# v1.net
KiCad netlist of a schematic drawn in EAGLE
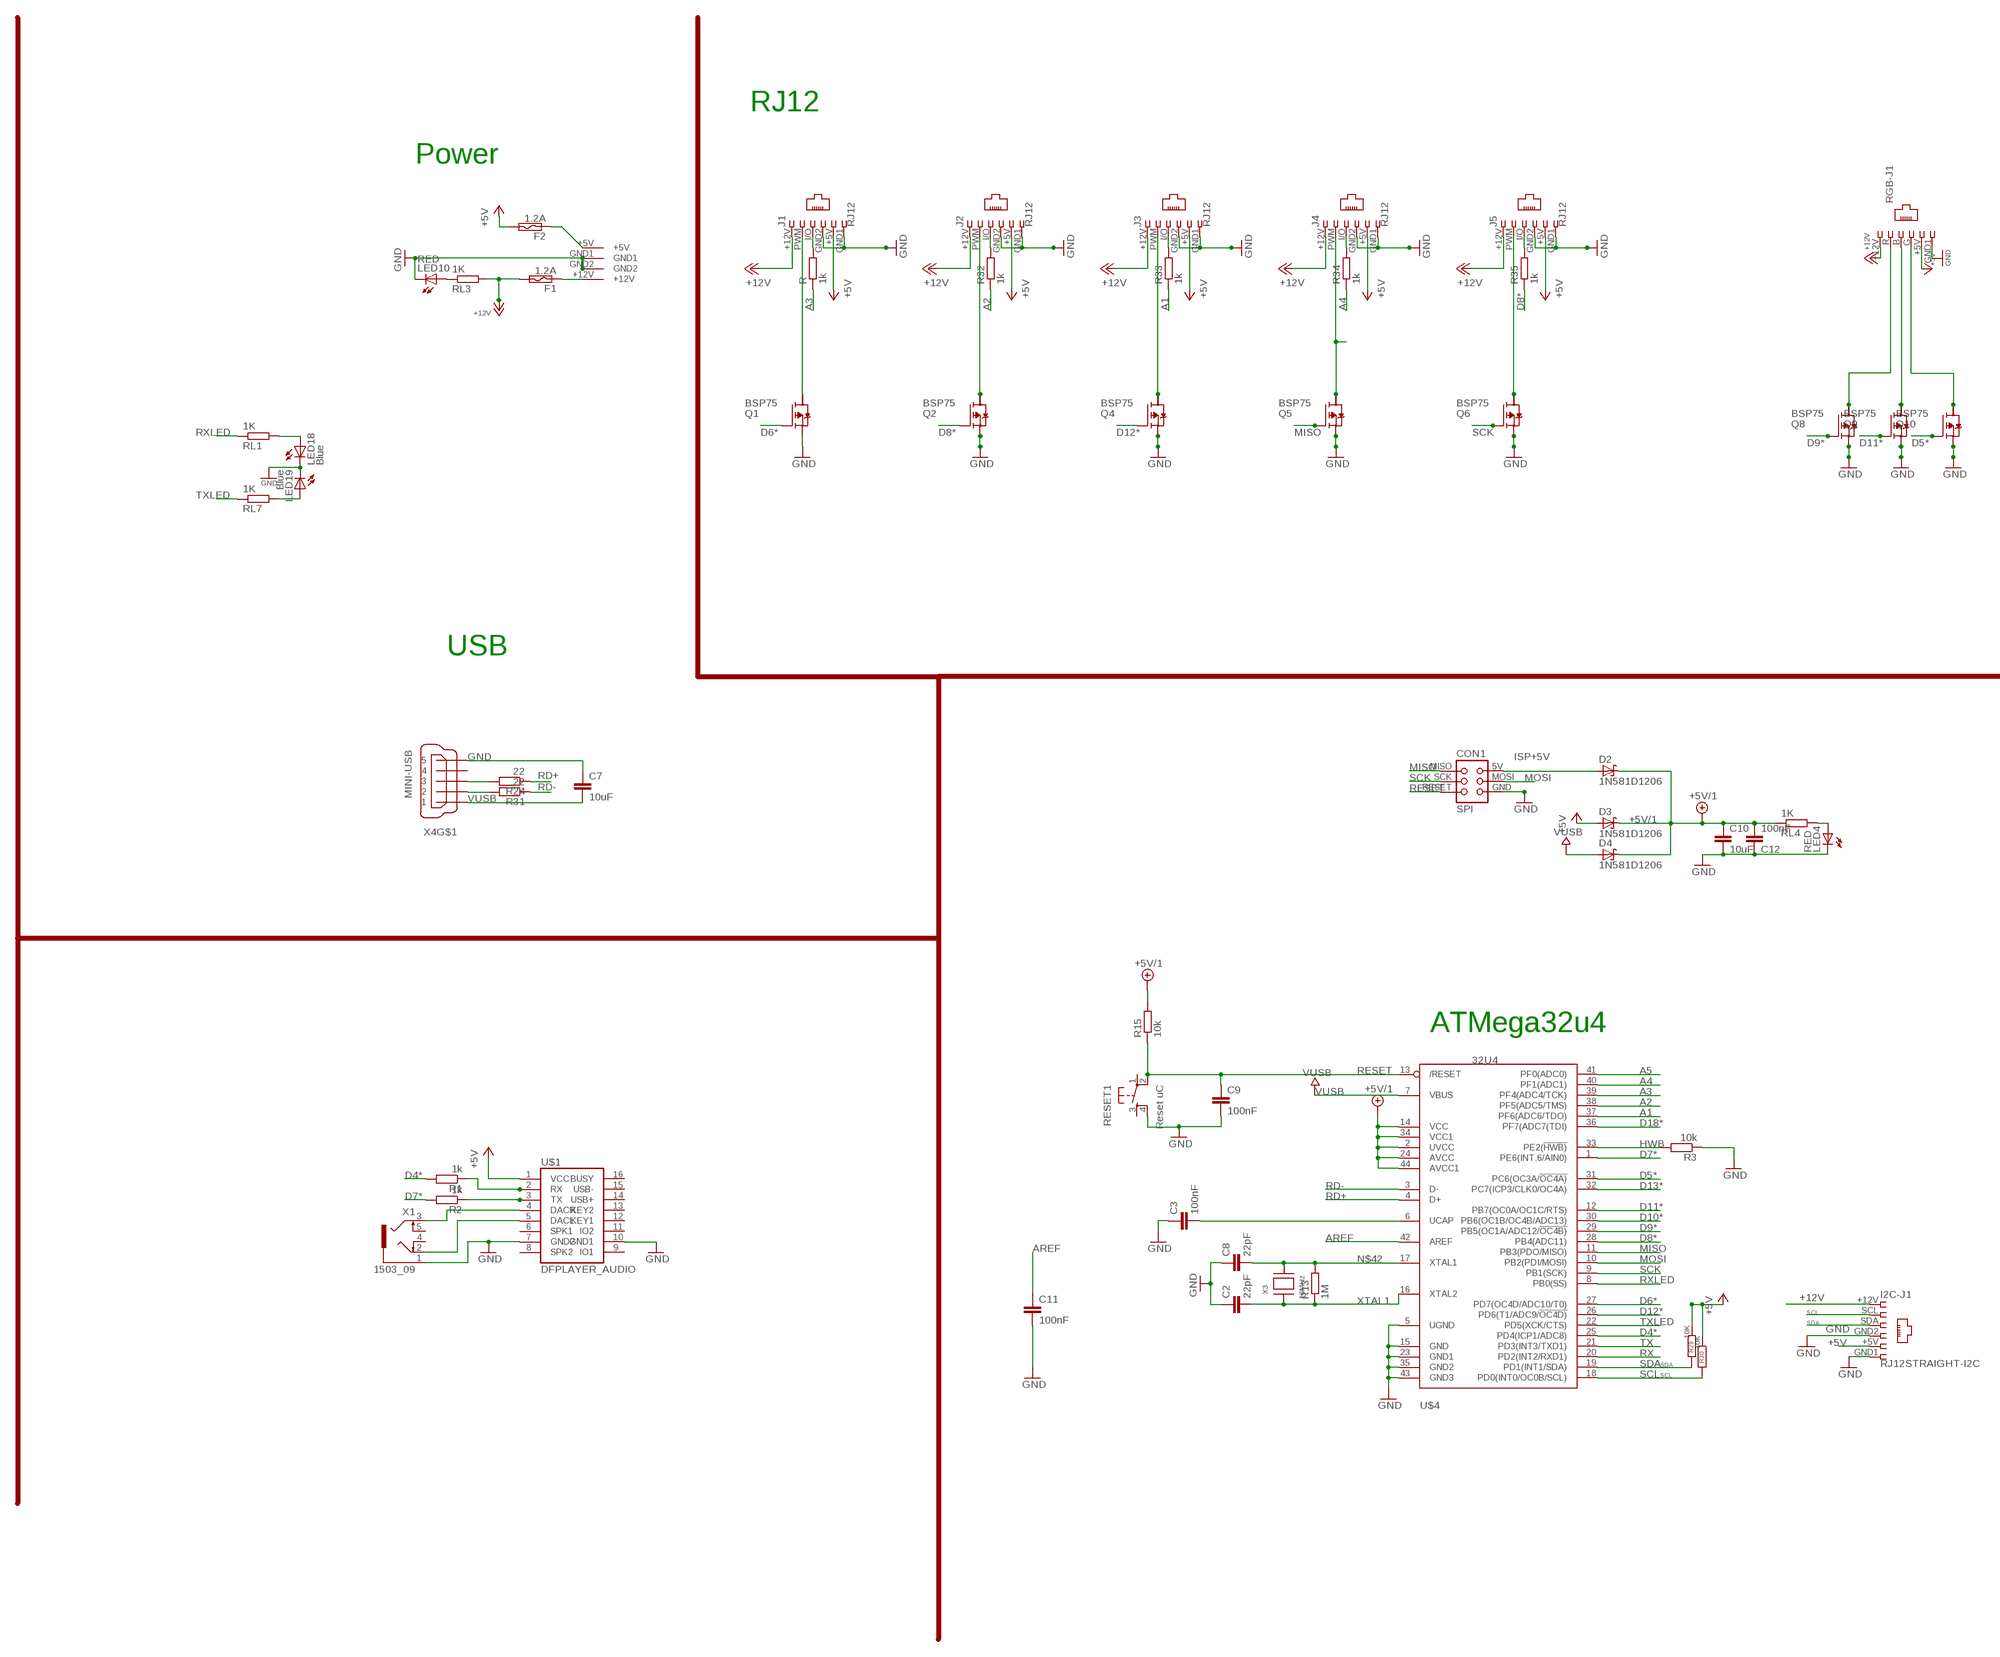
[diagram p0: schematic, sheet 1, part 1 of 2]
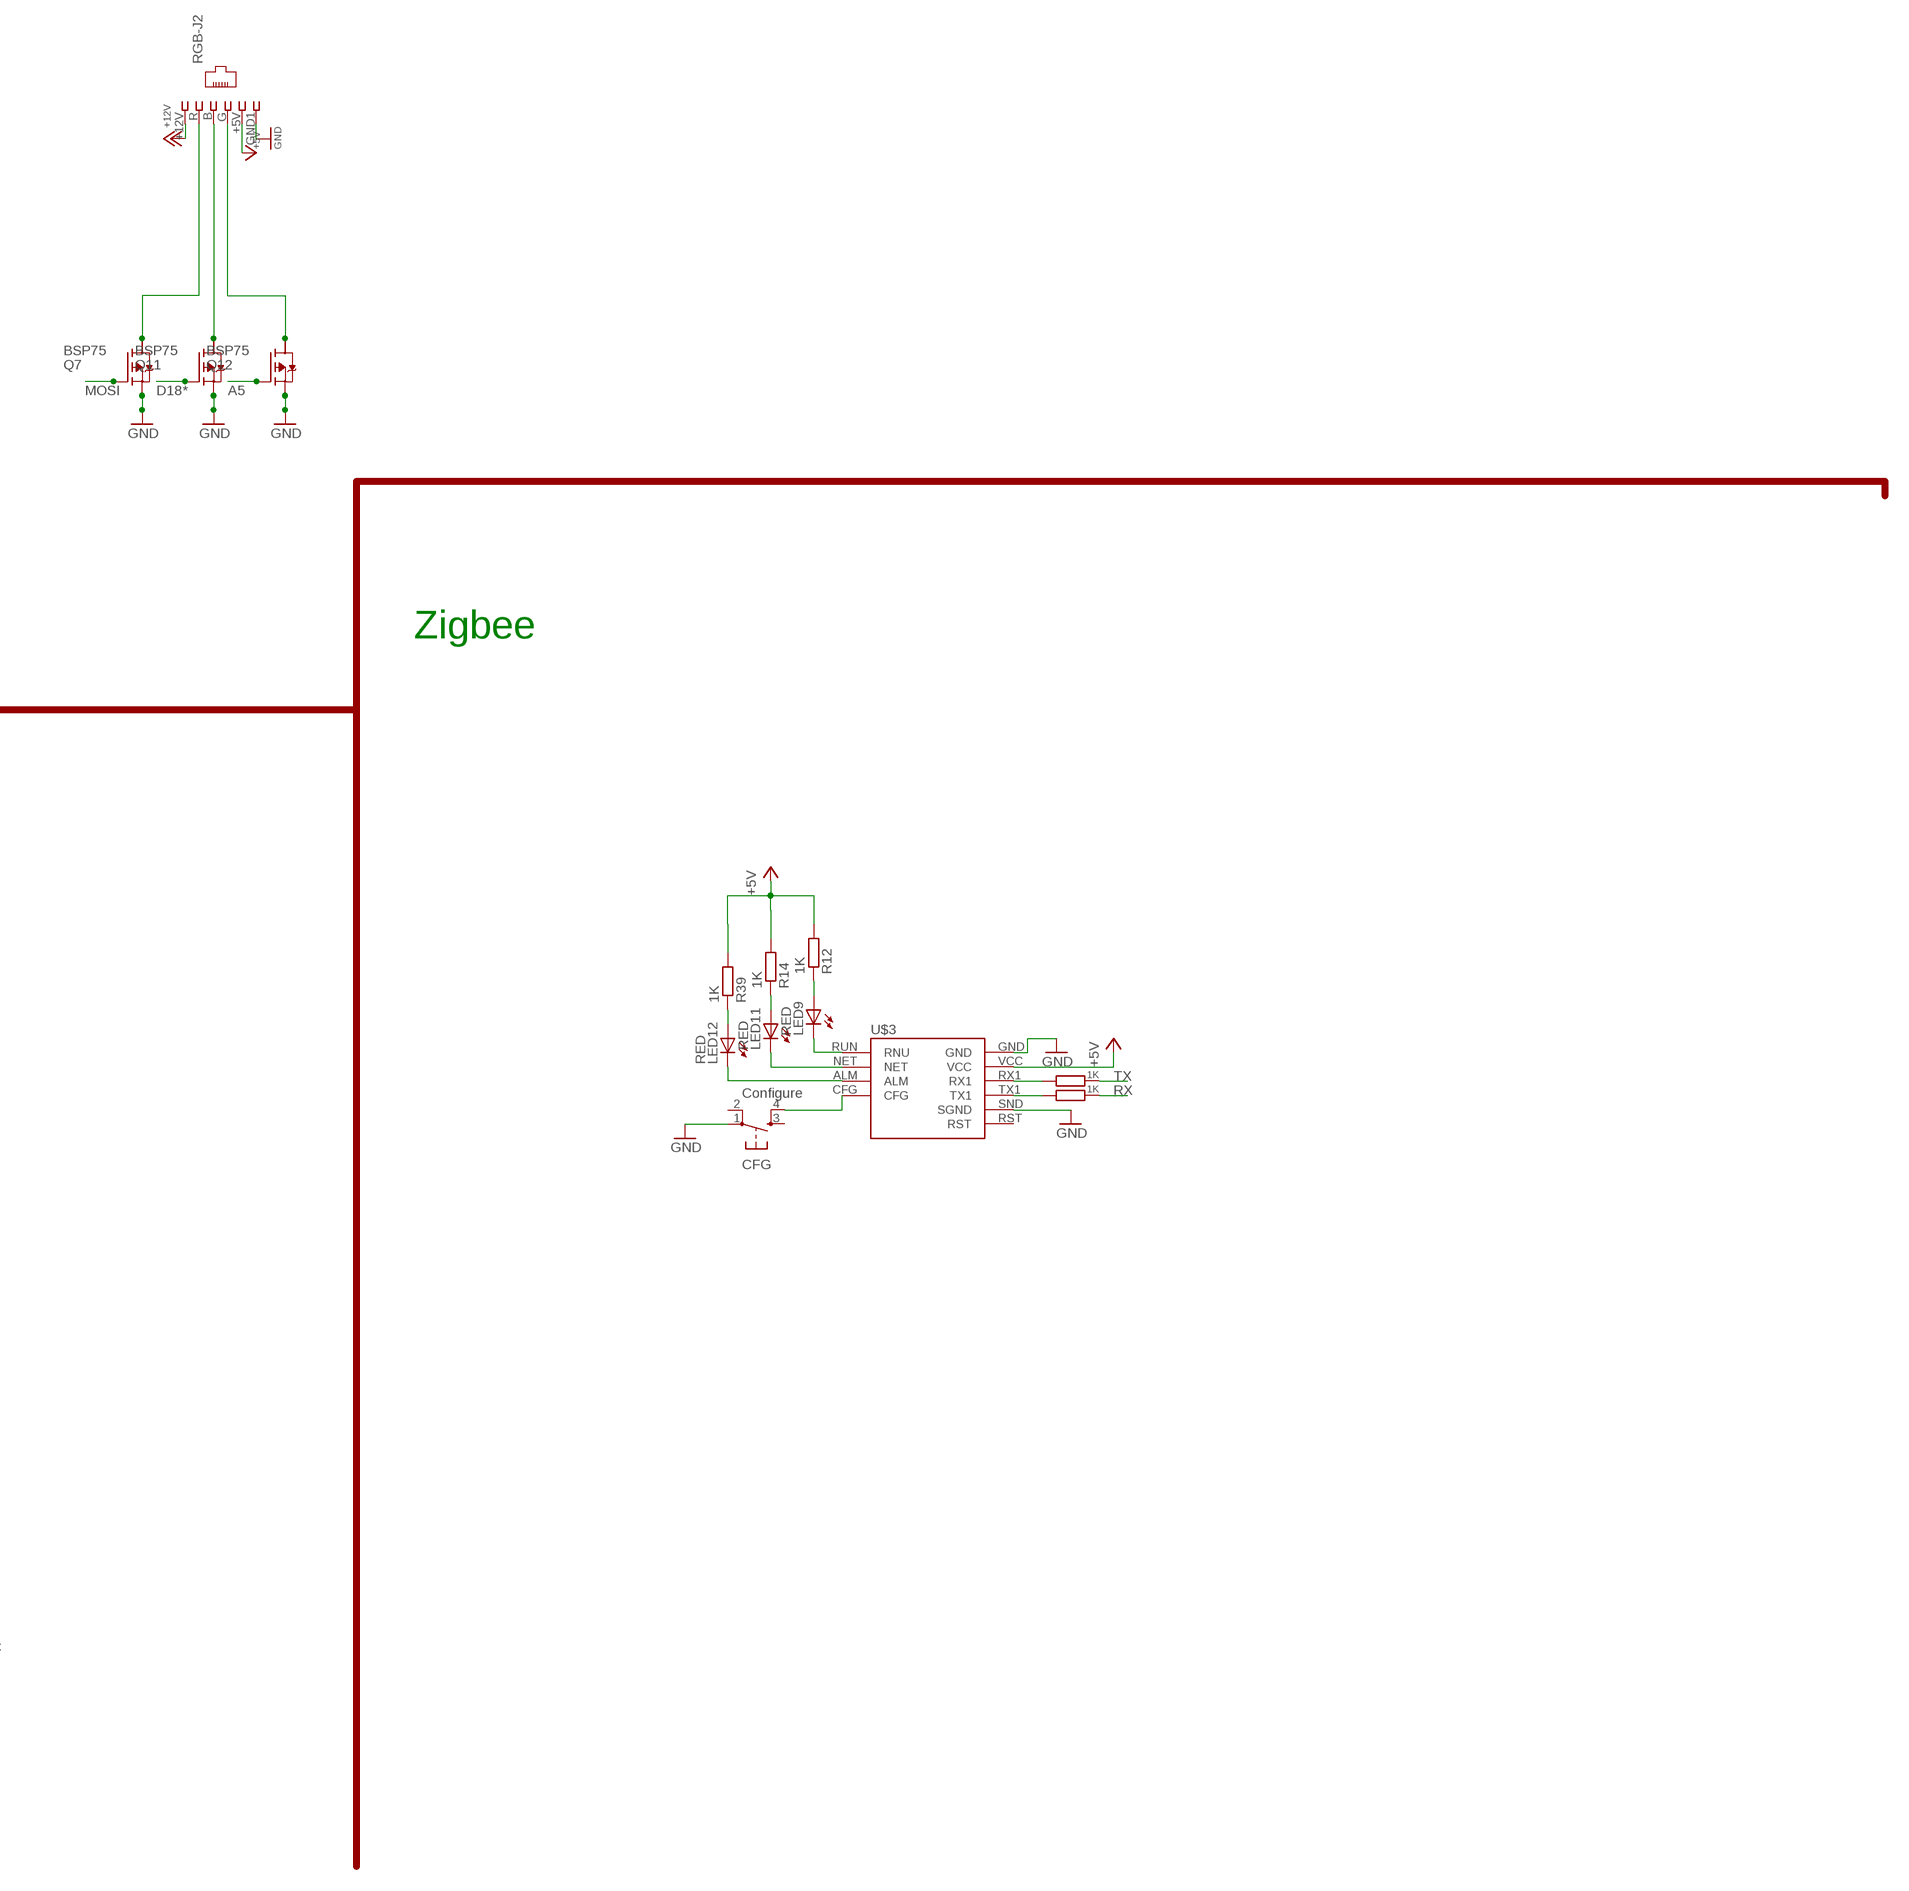
[diagram p1: schematic, sheet 1, part 2 of 2]

(export (version "E")
  (design (tool "Eeschema 10.0.6"))
  (components
    (comp (ref "C2")
      (value "22pF")
      (footprint "eagle-import:C1206")
      (libsource (lib "eagle-import") (part "C-EUC1206"))
    )
    (comp (ref "C3")
      (value "100nF")
      (footprint "eagle-import:C1206")
      (libsource (lib "eagle-import") (part "C-EUC1206"))
    )
    (comp (ref "C7")
      (value "10uF")
      (footprint "eagle-import:C1206")
      (libsource (lib "eagle-import") (part "C-EUC1206"))
    )
    (comp (ref "C8")
      (value "22pF")
      (footprint "eagle-import:C1206")
      (libsource (lib "eagle-import") (part "C-EUC1206"))
    )
    (comp (ref "C9")
      (value "100nF")
      (footprint "eagle-import:C1206")
      (libsource (lib "eagle-import") (part "C-EUC1206"))
    )
    (comp (ref "C10")
      (value "10uF")
      (footprint "eagle-import:C1206")
      (libsource (lib "eagle-import") (part "C-EUC1206"))
    )
    (comp (ref "C11")
      (value "100nF")
      (footprint "eagle-import:C1206")
      (libsource (lib "eagle-import") (part "C-EUC1206"))
    )
    (comp (ref "C12")
      (value "100nF")
      (footprint "eagle-import:C1206")
      (libsource (lib "eagle-import") (part "C-EUC1206"))
    )
    (comp (ref "CFG")
      (value "Configure")
      (footprint "eagle-import:TACTILE_SWITCH_SMD")
      (libsource (lib "eagle-import") (part "TAC_SWITCHSMD"))
    )
    (comp (ref "CON1")
      (value "SPI")
      (footprint "eagle-import:TC2030-MCP-NL")
      (libsource (lib "eagle-import") (part "TINYISPT"))
    )
    (comp (ref "D2")
      (value "1N581D1206")
      (footprint "eagle-import:LED-1206")
      (libsource (lib "eagle-import") (part "1N581D1206"))
    )
    (comp (ref "D3")
      (value "1N581D1206")
      (footprint "eagle-import:LED-1206")
      (libsource (lib "eagle-import") (part "1N581D1206"))
    )
    (comp (ref "D4")
      (value "1N581D1206")
      (footprint "eagle-import:LED-1206")
      (libsource (lib "eagle-import") (part "1N581D1206"))
    )
    (comp (ref "F1")
      (value "1.2A")
      (footprint "eagle-import:C1812")
      (libsource (lib "eagle-import") (part "POLYSWITCHSMD1812"))
    )
    (comp (ref "F2")
      (value "1.2A")
      (footprint "eagle-import:C1812")
      (libsource (lib "eagle-import") (part "POLYSWITCHSMD1812"))
    )
    (comp (ref "I2C-J1")
      (value "RJ12STRAIGHT-I2C")
      (footprint "eagle-import:RJ12-STRAIGHT-I2C")
      (libsource (lib "eagle-import") (part "RJ12STRAIGHT-I2C"))
    )
    (comp (ref "J1")
      (value "RJ12")
      (footprint "eagle-import:RJ12-STRAIGHT")
      (libsource (lib "eagle-import") (part "RJ12STRAIGHT"))
    )
    (comp (ref "J2")
      (value "RJ12")
      (footprint "eagle-import:RJ12-STRAIGHT")
      (libsource (lib "eagle-import") (part "RJ12STRAIGHT"))
    )
    (comp (ref "J3")
      (value "RJ12")
      (footprint "eagle-import:RJ12-STRAIGHT")
      (libsource (lib "eagle-import") (part "RJ12STRAIGHT"))
    )
    (comp (ref "J4")
      (value "RJ12")
      (footprint "eagle-import:RJ12-STRAIGHT")
      (libsource (lib "eagle-import") (part "RJ12STRAIGHT"))
    )
    (comp (ref "J5")
      (value "RJ12")
      (footprint "eagle-import:RJ12-STRAIGHT")
      (libsource (lib "eagle-import") (part "RJ12STRAIGHT"))
    )
    (comp (ref "LED4")
      (value "RED")
      (footprint "eagle-import:CHIP-LED0805")
      (libsource (lib "eagle-import") (part "LEDCHIP-LED0805"))
    )
    (comp (ref "LED9")
      (value "RED")
      (footprint "eagle-import:CHIP-LED0805")
      (libsource (lib "eagle-import") (part "LEDCHIP-LED0805"))
    )
    (comp (ref "LED10")
      (value "RED")
      (footprint "eagle-import:CHIP-LED0805")
      (libsource (lib "eagle-import") (part "LEDCHIP-LED0805"))
    )
    (comp (ref "LED11")
      (value "RED")
      (footprint "eagle-import:CHIP-LED0805")
      (libsource (lib "eagle-import") (part "LEDCHIP-LED0805"))
    )
    (comp (ref "LED12")
      (value "RED")
      (footprint "eagle-import:CHIP-LED0805")
      (libsource (lib "eagle-import") (part "LEDCHIP-LED0805"))
    )
    (comp (ref "LED18")
      (value "Blue")
      (footprint "eagle-import:CHIP-LED0805")
      (libsource (lib "eagle-import") (part "LEDCHIP-LED0805"))
    )
    (comp (ref "LED19")
      (value "Blue")
      (footprint "eagle-import:CHIP-LED0805")
      (libsource (lib "eagle-import") (part "LEDCHIP-LED0805"))
    )
    (comp (ref "Q1")
      (value "BSP75")
      (footprint "eagle-import:PG-SOT-223")
      (libsource (lib "eagle-import") (part "BSP613P"))
    )
    (comp (ref "Q2")
      (value "BSP75")
      (footprint "eagle-import:PG-SOT-223")
      (libsource (lib "eagle-import") (part "BSP613P"))
    )
    (comp (ref "Q4")
      (value "BSP75")
      (footprint "eagle-import:PG-SOT-223")
      (libsource (lib "eagle-import") (part "BSP613P"))
    )
    (comp (ref "Q5")
      (value "BSP75")
      (footprint "eagle-import:PG-SOT-223")
      (libsource (lib "eagle-import") (part "BSP613P"))
    )
    (comp (ref "Q6")
      (value "BSP75")
      (footprint "eagle-import:PG-SOT-223")
      (libsource (lib "eagle-import") (part "BSP613P"))
    )
    (comp (ref "Q7")
      (value "BSP75")
      (footprint "eagle-import:PG-SOT-223")
      (libsource (lib "eagle-import") (part "BSP613P"))
    )
    (comp (ref "Q8")
      (value "BSP75")
      (footprint "eagle-import:PG-SOT-223")
      (libsource (lib "eagle-import") (part "BSP613P"))
    )
    (comp (ref "Q9")
      (value "BSP75")
      (footprint "eagle-import:PG-SOT-223")
      (libsource (lib "eagle-import") (part "BSP613P"))
    )
    (comp (ref "Q10")
      (value "BSP75")
      (footprint "eagle-import:PG-SOT-223")
      (libsource (lib "eagle-import") (part "BSP613P"))
    )
    (comp (ref "Q11")
      (value "BSP75")
      (footprint "eagle-import:PG-SOT-223")
      (libsource (lib "eagle-import") (part "BSP613P"))
    )
    (comp (ref "Q12")
      (value "BSP75")
      (footprint "eagle-import:PG-SOT-223")
      (libsource (lib "eagle-import") (part "BSP613P"))
    )
    (comp (ref "R")
      (value "1k")
      (footprint "eagle-import:R0805")
      (libsource (lib "eagle-import") (part "R-EU_R0805"))
    )
    (comp (ref "R1")
      (value "1k")
      (footprint "eagle-import:R0805")
      (libsource (lib "eagle-import") (part "R-EU_R0805"))
    )
    (comp (ref "R2")
      (value "1k")
      (footprint "eagle-import:R0805")
      (libsource (lib "eagle-import") (part "R-EU_R0805"))
    )
    (comp (ref "R3")
      (value "10k")
      (footprint "eagle-import:M0805")
      (libsource (lib "eagle-import") (part "resistor_R-EU_M0805"))
    )
    (comp (ref "R8")
      (value "1K")
      (footprint "eagle-import:R0805")
      (libsource (lib "eagle-import") (part "R-EU_R0805"))
    )
    (comp (ref "R11")
      (value "1K")
      (footprint "eagle-import:R0805")
      (libsource (lib "eagle-import") (part "R-EU_R0805"))
    )
    (comp (ref "R12")
      (value "1K")
      (footprint "eagle-import:R0805")
      (libsource (lib "eagle-import") (part "R-EU_R0805"))
    )
    (comp (ref "R13")
      (value "1M")
      (footprint "eagle-import:R1206")
      (libsource (lib "eagle-import") (part "R-EU_R1206"))
    )
    (comp (ref "R14")
      (value "1K")
      (footprint "eagle-import:R0805")
      (libsource (lib "eagle-import") (part "R-EU_R0805"))
    )
    (comp (ref "R15")
      (value "10k")
      (footprint "eagle-import:M0805")
      (libsource (lib "eagle-import") (part "resistor_R-EU_M0805"))
    )
    (comp (ref "R24")
      (value "22")
      (footprint "eagle-import:M1206")
      (libsource (lib "eagle-import") (part "resistor_R-EU_M1206"))
    )
    (comp (ref "R29")
      (value "10K")
      (footprint "eagle-import:M0805")
      (libsource (lib "eagle-import") (part "resistor_R-EU_M0805"))
    )
    (comp (ref "R30")
      (value "10K")
      (footprint "eagle-import:M0805")
      (libsource (lib "eagle-import") (part "resistor_R-EU_M0805"))
    )
    (comp (ref "R31")
      (value "22")
      (footprint "eagle-import:M1206")
      (libsource (lib "eagle-import") (part "resistor_R-EU_M1206"))
    )
    (comp (ref "R32")
      (value "1k")
      (footprint "eagle-import:R0805")
      (libsource (lib "eagle-import") (part "R-EU_R0805"))
    )
    (comp (ref "R33")
      (value "1k")
      (footprint "eagle-import:R0805")
      (libsource (lib "eagle-import") (part "R-EU_R0805"))
    )
    (comp (ref "R34")
      (value "1k")
      (footprint "eagle-import:R0805")
      (libsource (lib "eagle-import") (part "R-EU_R0805"))
    )
    (comp (ref "R35")
      (value "1k")
      (footprint "eagle-import:R0805")
      (libsource (lib "eagle-import") (part "R-EU_R0805"))
    )
    (comp (ref "R39")
      (value "1K")
      (footprint "eagle-import:R0805")
      (libsource (lib "eagle-import") (part "R-EU_R0805"))
    )
    (comp (ref "RESET1")
      (value "Reset uC")
      (footprint "eagle-import:TACTILE_SWITCH_SMD")
      (libsource (lib "eagle-import") (part "TAC_SWITCHSMD"))
    )
    (comp (ref "RGB-J1")
      (value "RJ12")
      (footprint "eagle-import:RJ12-STRAIGHT-RGB")
      (libsource (lib "eagle-import") (part "RJ12STRAIGHT-RGB"))
    )
    (comp (ref "RGB-J2")
      (value "RJ12")
      (footprint "eagle-import:RJ12-STRAIGHT-RGB")
      (libsource (lib "eagle-import") (part "RJ12STRAIGHT-RGB"))
    )
    (comp (ref "RL1")
      (value "1K")
      (footprint "eagle-import:R0805")
      (libsource (lib "eagle-import") (part "R-EU_R0805"))
    )
    (comp (ref "RL3")
      (value "1K")
      (footprint "eagle-import:R0805")
      (libsource (lib "eagle-import") (part "R-EU_R0805"))
    )
    (comp (ref "RL4")
      (value "1K")
      (footprint "eagle-import:R0805")
      (libsource (lib "eagle-import") (part "resistor_R-EU_R0805"))
    )
    (comp (ref "RL7")
      (value "1K")
      (footprint "eagle-import:R0805")
      (libsource (lib "eagle-import") (part "R-EU_R0805"))
    )
    (comp (ref "U$1")
      (value "DFPLAYER_AUDIO")
      (footprint "eagle-import:DIL16-7")
      (libsource (lib "eagle-import") (part "DFPLAYER_AUDIO"))
    )
    (comp (ref "U$3")
      (value "SZ05-ZIGBEESMD")
      (footprint "eagle-import:SZ05-ZIGBEE3")
      (libsource (lib "eagle-import") (part "SZ05-ZIGBEESMD"))
    )
    (comp (ref "U$4")
      (value "32U4")
      (footprint "eagle-import:TQFP44")
      (libsource (lib "eagle-import") (part "ATMEGA32U4-AU"))
    )
    (comp (ref "U$6")
      (value "KPJX-4S-S")
      (footprint "eagle-import:KPJX-4S-S")
      (libsource (lib "eagle-import") (part "KPJX-4S-S"))
    )
    (comp (ref "X1")
      (value "1503_09")
      (footprint "eagle-import:1503_09")
      (libsource (lib "eagle-import") (part "1503_09"))
    )
    (comp (ref "X3")
      (value "16MHz")
      (footprint "eagle-import:NX6035")
      (libsource (lib "eagle-import") (part "XTALNX6035"))
    )
    (comp (ref "X4")
      (value "MINI-USB")
      (footprint "eagle-import:32005-201")
      (libsource (lib "eagle-import") (part "MINI-USB-SCHIELD-32005-201"))
    )
  )
  (nets
    (net (code "1") (name "+5V") (class "Default")
      (node (ref "D3") (pin "A") (pinfunction "A_A") (pintype "passive"))
      (node (ref "F2") (pin "2") (pinfunction "2_2") (pintype "passive"))
      (node (ref "I2C-J1") (pin "+5V") (pinfunction "5_+5V") (pintype "bidirectional"))
      (node (ref "J1") (pin "+5V") (pinfunction "5_+5V") (pintype "bidirectional"))
      (node (ref "J2") (pin "+5V") (pinfunction "5_+5V") (pintype "bidirectional"))
      (node (ref "J3") (pin "+5V") (pinfunction "5_+5V") (pintype "bidirectional"))
      (node (ref "J4") (pin "+5V") (pinfunction "5_+5V") (pintype "bidirectional"))
      (node (ref "J5") (pin "+5V") (pinfunction "5_+5V") (pintype "bidirectional"))
      (node (ref "R12") (pin "2") (pinfunction "2_2") (pintype "passive"))
      (node (ref "R14") (pin "2") (pinfunction "2_2") (pintype "passive"))
      (node (ref "R29") (pin "1") (pinfunction "1_1") (pintype "passive"))
      (node (ref "R30") (pin "1") (pinfunction "1_1") (pintype "passive"))
      (node (ref "R39") (pin "2") (pinfunction "2_2") (pintype "passive"))
      (node (ref "RGB-J1") (pin "+5V") (pinfunction "5_+5V") (pintype "bidirectional"))
      (node (ref "RGB-J2") (pin "+5V") (pinfunction "5_+5V") (pintype "bidirectional"))
      (node (ref "U$1") (pin "1") (pinfunction "VCC_1") (pintype "power_in"))
      (node (ref "U$3") (pin "VCC") (pinfunction "VCC_VCC") (pintype "bidirectional"))
    )
    (net (code "2") (name "+5V{slash}1") (class "Default")
      (node (ref "C10") (pin "1") (pinfunction "1_1") (pintype "passive"))
      (node (ref "C12") (pin "2") (pinfunction "2_2") (pintype "passive"))
      (node (ref "D2") (pin "C") (pinfunction "C_C") (pintype "passive"))
      (node (ref "D3") (pin "C") (pinfunction "C_C") (pintype "passive"))
      (node (ref "D4") (pin "C") (pinfunction "C_C") (pintype "passive"))
      (node (ref "R15") (pin "2") (pinfunction "2_2") (pintype "passive"))
      (node (ref "RL4") (pin "1") (pinfunction "1_1") (pintype "passive"))
      (node (ref "U$4") (pin "14") (pinfunction "VCC_14") (pintype "bidirectional"))
      (node (ref "U$4") (pin "2") (pinfunction "UVCC_2") (pintype "bidirectional"))
      (node (ref "U$4") (pin "24") (pinfunction "AVCC_24") (pintype "bidirectional"))
      (node (ref "U$4") (pin "34") (pinfunction "VCC1_34") (pintype "bidirectional"))
      (node (ref "U$4") (pin "44") (pinfunction "AVCC1_44") (pintype "bidirectional"))
    )
    (net (code "3") (name "+12V") (class "Default")
      (node (ref "F1") (pin "2") (pinfunction "2_2") (pintype "passive"))
      (node (ref "I2C-J1") (pin "+12V") (pinfunction "1_+12V") (pintype "bidirectional"))
      (node (ref "J1") (pin "+12V") (pinfunction "1_+12V") (pintype "bidirectional"))
      (node (ref "J2") (pin "+12V") (pinfunction "1_+12V") (pintype "bidirectional"))
      (node (ref "J3") (pin "+12V") (pinfunction "1_+12V") (pintype "bidirectional"))
      (node (ref "J4") (pin "+12V") (pinfunction "1_+12V") (pintype "bidirectional"))
      (node (ref "J5") (pin "+12V") (pinfunction "1_+12V") (pintype "bidirectional"))
      (node (ref "RGB-J1") (pin "+12V") (pinfunction "1_+12V") (pintype "bidirectional"))
      (node (ref "RGB-J2") (pin "+12V") (pinfunction "1_+12V") (pintype "bidirectional"))
      (node (ref "RL3") (pin "2") (pinfunction "2_2") (pintype "passive"))
    )
    (net (code "4") (name "/A1") (class "Default")
      (node (ref "R33") (pin "1") (pinfunction "1_1") (pintype "passive"))
      (node (ref "U$4") (pin "37") (pinfunction "PF6(ADC6/TDO)_37") (pintype "bidirectional"))
    )
    (net (code "5") (name "/A2") (class "Default")
      (node (ref "R32") (pin "1") (pinfunction "1_1") (pintype "passive"))
      (node (ref "U$4") (pin "38") (pinfunction "PF5(ADC5/TMS)_38") (pintype "bidirectional"))
    )
    (net (code "6") (name "/A3") (class "Default")
      (node (ref "R") (pin "1") (pinfunction "1_1") (pintype "passive"))
      (node (ref "U$4") (pin "39") (pinfunction "PF4(ADC4/TCK)_39") (pintype "bidirectional"))
    )
    (net (code "7") (name "/A4") (class "Default")
      (node (ref "R34") (pin "1") (pinfunction "1_1") (pintype "passive"))
      (node (ref "U$4") (pin "40") (pinfunction "PF1(ADC1)_40") (pintype "bidirectional"))
    )
    (net (code "8") (name "/A5") (class "Default")
      (node (ref "Q12") (pin "1") (pinfunction "G_1") (pintype "passive"))
      (node (ref "U$4") (pin "41") (pinfunction "PF0(ADC0)_41") (pintype "bidirectional"))
    )
    (net (code "9") (name "/AREF") (class "Default")
      (node (ref "C11") (pin "1") (pinfunction "1_1") (pintype "passive"))
      (node (ref "U$4") (pin "42") (pinfunction "AREF_42") (pintype "bidirectional"))
    )
    (net (code "10") (name "/D4*") (class "Default")
      (node (ref "R1") (pin "2") (pinfunction "2_2") (pintype "passive"))
      (node (ref "U$4") (pin "25") (pinfunction "PD4(ICP1/ADC8)_25") (pintype "bidirectional"))
    )
    (net (code "11") (name "/D5*") (class "Default")
      (node (ref "Q10") (pin "1") (pinfunction "G_1") (pintype "passive"))
      (node (ref "U$4") (pin "31") (pinfunction "PC6(OC3A/~{OC4A})_31") (pintype "bidirectional"))
    )
    (net (code "12") (name "/D6*") (class "Default")
      (node (ref "Q1") (pin "1") (pinfunction "G_1") (pintype "passive"))
      (node (ref "U$4") (pin "27") (pinfunction "PD7(OC4D/ADC10/T0)_27") (pintype "bidirectional"))
    )
    (net (code "13") (name "/D7*") (class "Default")
      (node (ref "R2") (pin "2") (pinfunction "2_2") (pintype "passive"))
      (node (ref "U$4") (pin "1") (pinfunction "PE6(INT.6/AIN0)_1") (pintype "bidirectional"))
    )
    (net (code "14") (name "/D8*") (class "Default")
      (node (ref "Q2") (pin "1") (pinfunction "G_1") (pintype "passive"))
      (node (ref "R35") (pin "1") (pinfunction "1_1") (pintype "passive"))
      (node (ref "U$4") (pin "28") (pinfunction "PB4(ADC11)_28") (pintype "bidirectional"))
    )
    (net (code "15") (name "/D9*") (class "Default")
      (node (ref "Q8") (pin "1") (pinfunction "G_1") (pintype "passive"))
      (node (ref "U$4") (pin "29") (pinfunction "PB5(OC1A/ADC12/~{OC4B})_29") (pintype "bidirectional"))
    )
    (net (code "16") (name "/D10*") (class "Default")
      (node (ref "U$4") (pin "30") (pinfunction "PB6(OC1B/OC4B/ADC13)_30") (pintype "bidirectional"))
    )
    (net (code "17") (name "/D11*") (class "Default")
      (node (ref "Q9") (pin "1") (pinfunction "G_1") (pintype "passive"))
      (node (ref "U$4") (pin "12") (pinfunction "PB7(OC0A/OC1C/RTS)_12") (pintype "bidirectional"))
    )
    (net (code "18") (name "/D12*") (class "Default")
      (node (ref "Q4") (pin "1") (pinfunction "G_1") (pintype "passive"))
      (node (ref "U$4") (pin "26") (pinfunction "PD6(T1/ADC9/~{OC4D})_26") (pintype "bidirectional"))
    )
    (net (code "19") (name "/D13*") (class "Default")
      (node (ref "U$4") (pin "32") (pinfunction "PC7(ICP3/CLK0/OC4A)_32") (pintype "bidirectional"))
    )
    (net (code "20") (name "/D18*") (class "Default")
      (node (ref "Q11") (pin "1") (pinfunction "G_1") (pintype "passive"))
      (node (ref "U$4") (pin "36") (pinfunction "PF7(ADC7(TDI)_36") (pintype "bidirectional"))
    )
    (net (code "21") (name "/HWB") (class "Default")
      (node (ref "R3") (pin "2") (pinfunction "2_2") (pintype "passive"))
      (node (ref "U$4") (pin "33") (pinfunction "PE2(~{HWB})_33") (pintype "bidirectional"))
    )
    (net (code "22") (name "/ISP+5V") (class "Default")
      (node (ref "CON1") (pin "5V") (pinfunction "VCC_5V") (pintype "passive"))
      (node (ref "D2") (pin "A") (pinfunction "A_A") (pintype "passive"))
    )
    (net (code "23") (name "/MISO") (class "Default")
      (node (ref "CON1") (pin "MISO") (pinfunction "MISO_MISO") (pintype "passive"))
      (node (ref "Q5") (pin "1") (pinfunction "G_1") (pintype "passive"))
      (node (ref "U$4") (pin "11") (pinfunction "PB3(PDO/MISO)_11") (pintype "bidirectional"))
    )
    (net (code "24") (name "/MOSI") (class "Default")
      (node (ref "CON1") (pin "MOSI") (pinfunction "MOSI_MOSI") (pintype "passive"))
      (node (ref "Q7") (pin "1") (pinfunction "G_1") (pintype "passive"))
      (node (ref "U$4") (pin "10") (pinfunction "PB2(PDI/MOSI)_10") (pintype "bidirectional"))
    )
    (net (code "25") (name "/N$42") (class "Default")
      (node (ref "C8") (pin "2") (pinfunction "2_2") (pintype "passive"))
      (node (ref "R13") (pin "2") (pinfunction "2_2") (pintype "passive"))
      (node (ref "U$4") (pin "17") (pinfunction "XTAL1_17") (pintype "bidirectional"))
      (node (ref "X3") (pin "P$2") (pinfunction "P$2_P$2") (pintype "bidirectional"))
    )
    (net (code "26") (name "/RD+") (class "Default")
      (node (ref "R24") (pin "1") (pinfunction "1_1") (pintype "passive"))
      (node (ref "U$4") (pin "4") (pinfunction "D+_4") (pintype "bidirectional"))
    )
    (net (code "27") (name "/RD-") (class "Default")
      (node (ref "R31") (pin "1") (pinfunction "1_1") (pintype "passive"))
      (node (ref "U$4") (pin "3") (pinfunction "D-_3") (pintype "bidirectional"))
    )
    (net (code "28") (name "/RESET") (class "Default")
      (node (ref "C9") (pin "1") (pinfunction "1_1") (pintype "passive"))
      (node (ref "CON1") (pin "RESET") (pinfunction "RESET_RESET") (pintype "passive"))
      (node (ref "R15") (pin "1") (pinfunction "1_1") (pintype "passive"))
      (node (ref "RESET1") (pin "2") (pinfunction "2_2") (pintype "passive"))
      (node (ref "U$4") (pin "13") (pinfunction "/RESET_13") (pintype "bidirectional"))
    )
    (net (code "29") (name "/RX") (class "Default")
      (node (ref "R8") (pin "1") (pinfunction "1_1") (pintype "passive"))
      (node (ref "U$4") (pin "20") (pinfunction "PD2(INT2/RXD1)_20") (pintype "bidirectional"))
    )
    (net (code "30") (name "/RXLED") (class "Default")
      (node (ref "RL1") (pin "1") (pinfunction "1_1") (pintype "passive"))
      (node (ref "U$4") (pin "8") (pinfunction "PB0(SS)_8") (pintype "bidirectional"))
    )
    (net (code "31") (name "/SCK") (class "Default")
      (node (ref "CON1") (pin "SCK") (pinfunction "SCK_SCK") (pintype "passive"))
      (node (ref "Q6") (pin "1") (pinfunction "G_1") (pintype "passive"))
      (node (ref "U$4") (pin "9") (pinfunction "PB1(SCK)_9") (pintype "bidirectional"))
    )
    (net (code "32") (name "/SCL") (class "Default")
      (node (ref "I2C-J1") (pin "SCL") (pinfunction "2_SCL") (pintype "bidirectional"))
      (node (ref "R30") (pin "2") (pinfunction "2_2") (pintype "passive"))
      (node (ref "U$4") (pin "18") (pinfunction "PD0(INT0/OC0B/SCL)_18") (pintype "bidirectional"))
    )
    (net (code "33") (name "/SDA") (class "Default")
      (node (ref "I2C-J1") (pin "SDA") (pinfunction "3_SDA") (pintype "bidirectional"))
      (node (ref "R29") (pin "2") (pinfunction "2_2") (pintype "passive"))
      (node (ref "U$4") (pin "19") (pinfunction "PD1(INT1/SDA)_19") (pintype "bidirectional"))
    )
    (net (code "34") (name "/TX") (class "Default")
      (node (ref "R11") (pin "1") (pinfunction "1_1") (pintype "passive"))
      (node (ref "U$4") (pin "21") (pinfunction "PD3(INT3/TXD1)_21") (pintype "bidirectional"))
    )
    (net (code "35") (name "/TXLED") (class "Default")
      (node (ref "RL7") (pin "1") (pinfunction "1_1") (pintype "passive"))
      (node (ref "U$4") (pin "22") (pinfunction "PD5(XCK/CTS)_22") (pintype "bidirectional"))
    )
    (net (code "36") (name "/XTAL1") (class "Default")
      (node (ref "C2") (pin "2") (pinfunction "2_2") (pintype "passive"))
      (node (ref "R13") (pin "1") (pinfunction "1_1") (pintype "passive"))
      (node (ref "U$4") (pin "16") (pinfunction "XTAL2_16") (pintype "bidirectional"))
      (node (ref "X3") (pin "P$1") (pinfunction "P$1_P$1") (pintype "bidirectional"))
    )
    (net (code "37") (name "GND") (class "Default")
      (node (ref "C10") (pin "2") (pinfunction "2_2") (pintype "passive"))
      (node (ref "C11") (pin "2") (pinfunction "2_2") (pintype "passive"))
      (node (ref "C12") (pin "1") (pinfunction "1_1") (pintype "passive"))
      (node (ref "C2") (pin "1") (pinfunction "1_1") (pintype "passive"))
      (node (ref "C3") (pin "1") (pinfunction "1_1") (pintype "passive"))
      (node (ref "C7") (pin "1") (pinfunction "1_1") (pintype "passive"))
      (node (ref "C8") (pin "1") (pinfunction "1_1") (pintype "passive"))
      (node (ref "C9") (pin "2") (pinfunction "2_2") (pintype "passive"))
      (node (ref "CFG") (pin "1") (pinfunction "1_1") (pintype "passive"))
      (node (ref "CON1") (pin "GND") (pinfunction "GND_GND") (pintype "passive"))
      (node (ref "I2C-J1") (pin "GND1") (pinfunction "6_GND1") (pintype "bidirectional"))
      (node (ref "I2C-J1") (pin "GND2") (pinfunction "4_GND2") (pintype "bidirectional"))
      (node (ref "J1") (pin "GND1") (pinfunction "6_GND1") (pintype "bidirectional"))
      (node (ref "J1") (pin "GND2") (pinfunction "4_GND2") (pintype "bidirectional"))
      (node (ref "J2") (pin "GND1") (pinfunction "6_GND1") (pintype "bidirectional"))
      (node (ref "J2") (pin "GND2") (pinfunction "4_GND2") (pintype "bidirectional"))
      (node (ref "J3") (pin "GND1") (pinfunction "6_GND1") (pintype "bidirectional"))
      (node (ref "J3") (pin "GND2") (pinfunction "4_GND2") (pintype "bidirectional"))
      (node (ref "J4") (pin "GND1") (pinfunction "6_GND1") (pintype "bidirectional"))
      (node (ref "J4") (pin "GND2") (pinfunction "4_GND2") (pintype "bidirectional"))
      (node (ref "J5") (pin "GND1") (pinfunction "6_GND1") (pintype "bidirectional"))
      (node (ref "J5") (pin "GND2") (pinfunction "4_GND2") (pintype "bidirectional"))
      (node (ref "LED10") (pin "C") (pinfunction "C_C") (pintype "passive"))
      (node (ref "LED18") (pin "C") (pinfunction "C_C") (pintype "passive"))
      (node (ref "LED19") (pin "C") (pinfunction "C_C") (pintype "passive"))
      (node (ref "LED4") (pin "C") (pinfunction "C_C") (pintype "passive"))
      (node (ref "Q1") (pin "3") (pinfunction "S_3") (pintype "passive"))
      (node (ref "Q10") (pin "3") (pinfunction "S_3") (pintype "passive"))
      (node (ref "Q11") (pin "3") (pinfunction "S_3") (pintype "passive"))
      (node (ref "Q12") (pin "3") (pinfunction "S_3") (pintype "passive"))
      (node (ref "Q2") (pin "3") (pinfunction "S_3") (pintype "passive"))
      (node (ref "Q4") (pin "3") (pinfunction "S_3") (pintype "passive"))
      (node (ref "Q5") (pin "3") (pinfunction "S_3") (pintype "passive"))
      (node (ref "Q6") (pin "3") (pinfunction "S_3") (pintype "passive"))
      (node (ref "Q7") (pin "3") (pinfunction "S_3") (pintype "passive"))
      (node (ref "Q8") (pin "3") (pinfunction "S_3") (pintype "passive"))
      (node (ref "Q9") (pin "3") (pinfunction "S_3") (pintype "passive"))
      (node (ref "R3") (pin "1") (pinfunction "1_1") (pintype "passive"))
      (node (ref "RESET1") (pin "4") (pinfunction "4_4") (pintype "passive"))
      (node (ref "RGB-J1") (pin "GND1") (pinfunction "6_GND1") (pintype "bidirectional"))
      (node (ref "RGB-J2") (pin "GND1") (pinfunction "6_GND1") (pintype "bidirectional"))
      (node (ref "U$1") (pin "10") (pinfunction "GND1_10") (pintype "power_in"))
      (node (ref "U$1") (pin "7") (pinfunction "GND2_7") (pintype "power_in"))
      (node (ref "U$3") (pin "GND") (pinfunction "GND_GND") (pintype "bidirectional"))
      (node (ref "U$3") (pin "SND") (pinfunction "SGND_SND") (pintype "bidirectional"))
      (node (ref "U$4") (pin "15") (pinfunction "GND_15") (pintype "bidirectional"))
      (node (ref "U$4") (pin "23") (pinfunction "GND1_23") (pintype "bidirectional"))
      (node (ref "U$4") (pin "35") (pinfunction "GND2_35") (pintype "bidirectional"))
      (node (ref "U$4") (pin "43") (pinfunction "GND3_43") (pintype "bidirectional"))
      (node (ref "U$4") (pin "5") (pinfunction "UGND_5") (pintype "bidirectional"))
      (node (ref "U$6") (pin "GND1") (pinfunction "GND1_GND1") (pintype "input"))
      (node (ref "U$6") (pin "GND2") (pinfunction "GND2_GND2") (pintype "input"))
      (node (ref "X1") (pin "1") (pinfunction "1_1") (pintype "passive"))
      (node (ref "X4") (pin "5") (pinfunction "5_5") (pintype "passive"))
    )
    (net (code "38") (name "Net-(CFG-Pad4)") (class "Default")
      (node (ref "CFG") (pin "4") (pinfunction "4_4") (pintype "passive"))
      (node (ref "U$3") (pin "CFG") (pinfunction "CFG_CFG") (pintype "bidirectional"))
    )
    (net (code "39") (name "Net-(F1-Pad1)") (class "Default")
      (node (ref "F1") (pin "1") (pinfunction "1_1") (pintype "passive"))
      (node (ref "U$6") (pin "+12V") (pinfunction "+12V_+12V") (pintype "power_in"))
    )
    (net (code "40") (name "Net-(F2-Pad1)") (class "Default")
      (node (ref "F2") (pin "1") (pinfunction "1_1") (pintype "passive"))
      (node (ref "U$6") (pin "+5V") (pinfunction "+5V_+5V") (pintype "power_in"))
    )
    (net (code "41") (name "Net-(J1-2)") (class "Default")
      (node (ref "J1") (pin "PWM") (pinfunction "2_PWM") (pintype "bidirectional"))
      (node (ref "Q1") (pin "2") (pinfunction "D_2") (pintype "passive"))
    )
    (net (code "42") (name "Net-(J1-3)") (class "Default")
      (node (ref "J1") (pin "I/O") (pinfunction "3_I/O") (pintype "bidirectional"))
      (node (ref "R") (pin "2") (pinfunction "2_2") (pintype "passive"))
    )
    (net (code "43") (name "Net-(J2-2)") (class "Default")
      (node (ref "J2") (pin "PWM") (pinfunction "2_PWM") (pintype "bidirectional"))
      (node (ref "Q2") (pin "2") (pinfunction "D_2") (pintype "passive"))
    )
    (net (code "44") (name "Net-(J2-3)") (class "Default")
      (node (ref "J2") (pin "I/O") (pinfunction "3_I/O") (pintype "bidirectional"))
      (node (ref "R32") (pin "2") (pinfunction "2_2") (pintype "passive"))
    )
    (net (code "45") (name "Net-(J3-2)") (class "Default")
      (node (ref "J3") (pin "PWM") (pinfunction "2_PWM") (pintype "bidirectional"))
      (node (ref "Q4") (pin "2") (pinfunction "D_2") (pintype "passive"))
    )
    (net (code "46") (name "Net-(J3-3)") (class "Default")
      (node (ref "J3") (pin "I/O") (pinfunction "3_I/O") (pintype "bidirectional"))
      (node (ref "R33") (pin "2") (pinfunction "2_2") (pintype "passive"))
    )
    (net (code "47") (name "Net-(J4-2)") (class "Default")
      (node (ref "J4") (pin "PWM") (pinfunction "2_PWM") (pintype "bidirectional"))
      (node (ref "Q5") (pin "2") (pinfunction "D_2") (pintype "passive"))
    )
    (net (code "48") (name "Net-(J4-3)") (class "Default")
      (node (ref "J4") (pin "I/O") (pinfunction "3_I/O") (pintype "bidirectional"))
      (node (ref "R34") (pin "2") (pinfunction "2_2") (pintype "passive"))
    )
    (net (code "49") (name "Net-(J5-2)") (class "Default")
      (node (ref "J5") (pin "PWM") (pinfunction "2_PWM") (pintype "bidirectional"))
      (node (ref "Q6") (pin "2") (pinfunction "D_2") (pintype "passive"))
    )
    (net (code "50") (name "Net-(J5-3)") (class "Default")
      (node (ref "J5") (pin "I/O") (pinfunction "3_I/O") (pintype "bidirectional"))
      (node (ref "R35") (pin "2") (pinfunction "2_2") (pintype "passive"))
    )
    (net (code "51") (name "Net-(LED4-PadA)") (class "Default")
      (node (ref "LED4") (pin "A") (pinfunction "A_A") (pintype "passive"))
      (node (ref "RL4") (pin "2") (pinfunction "2_2") (pintype "passive"))
    )
    (net (code "52") (name "Net-(LED9-PadA)") (class "Default")
      (node (ref "LED9") (pin "A") (pinfunction "A_A") (pintype "passive"))
      (node (ref "R12") (pin "1") (pinfunction "1_1") (pintype "passive"))
    )
    (net (code "53") (name "Net-(LED10-PadA)") (class "Default")
      (node (ref "LED10") (pin "A") (pinfunction "A_A") (pintype "passive"))
      (node (ref "RL3") (pin "1") (pinfunction "1_1") (pintype "passive"))
    )
    (net (code "54") (name "Net-(LED11-PadA)") (class "Default")
      (node (ref "LED11") (pin "A") (pinfunction "A_A") (pintype "passive"))
      (node (ref "R14") (pin "1") (pinfunction "1_1") (pintype "passive"))
    )
    (net (code "55") (name "Net-(LED11-PadC)") (class "Default")
      (node (ref "LED11") (pin "C") (pinfunction "C_C") (pintype "passive"))
      (node (ref "U$3") (pin "NET") (pinfunction "NET_NET") (pintype "bidirectional"))
    )
    (net (code "56") (name "Net-(LED12-PadA)") (class "Default")
      (node (ref "LED12") (pin "A") (pinfunction "A_A") (pintype "passive"))
      (node (ref "R39") (pin "1") (pinfunction "1_1") (pintype "passive"))
    )
    (net (code "57") (name "Net-(LED12-PadC)") (class "Default")
      (node (ref "LED12") (pin "C") (pinfunction "C_C") (pintype "passive"))
      (node (ref "U$3") (pin "ALM") (pinfunction "ALM_ALM") (pintype "bidirectional"))
    )
    (net (code "58") (name "Net-(LED18-PadA)") (class "Default")
      (node (ref "LED18") (pin "A") (pinfunction "A_A") (pintype "passive"))
      (node (ref "RL1") (pin "2") (pinfunction "2_2") (pintype "passive"))
    )
    (net (code "59") (name "Net-(LED19-PadA)") (class "Default")
      (node (ref "LED19") (pin "A") (pinfunction "A_A") (pintype "passive"))
      (node (ref "RL7") (pin "2") (pinfunction "2_2") (pintype "passive"))
    )
    (net (code "60") (name "Net-(R8-Pad2)") (class "Default")
      (node (ref "R8") (pin "2") (pinfunction "2_2") (pintype "passive"))
      (node (ref "U$3") (pin "TX1") (pinfunction "TX1_TX1") (pintype "bidirectional"))
    )
    (net (code "61") (name "Net-(R11-Pad2)") (class "Default")
      (node (ref "R11") (pin "2") (pinfunction "2_2") (pintype "passive"))
      (node (ref "U$3") (pin "RX1") (pinfunction "RX1_RX1") (pintype "bidirectional"))
    )
    (net (code "62") (name "Net-(R24-Pad2)") (class "Default")
      (node (ref "R24") (pin "2") (pinfunction "2_2") (pintype "passive"))
      (node (ref "X4") (pin "3") (pinfunction "3_3") (pintype "passive"))
    )
    (net (code "63") (name "Net-(R31-Pad2)") (class "Default")
      (node (ref "R31") (pin "2") (pinfunction "2_2") (pintype "passive"))
      (node (ref "X4") (pin "2") (pinfunction "2_2") (pintype "passive"))
    )
    (net (code "64") (name "Net-(RGB-J1-2)") (class "Default")
      (node (ref "Q8") (pin "2") (pinfunction "D_2") (pintype "passive"))
      (node (ref "RGB-J1") (pin "R") (pinfunction "2_R") (pintype "bidirectional"))
    )
    (net (code "65") (name "Net-(RGB-J1-3)") (class "Default")
      (node (ref "Q9") (pin "2") (pinfunction "D_2") (pintype "passive"))
      (node (ref "RGB-J1") (pin "B") (pinfunction "3_B") (pintype "bidirectional"))
    )
    (net (code "66") (name "Net-(RGB-J1-4)") (class "Default")
      (node (ref "Q10") (pin "2") (pinfunction "D_2") (pintype "passive"))
      (node (ref "RGB-J1") (pin "G") (pinfunction "4_G") (pintype "bidirectional"))
    )
    (net (code "67") (name "Net-(RGB-J2-2)") (class "Default")
      (node (ref "Q7") (pin "2") (pinfunction "D_2") (pintype "passive"))
      (node (ref "RGB-J2") (pin "R") (pinfunction "2_R") (pintype "bidirectional"))
    )
    (net (code "68") (name "Net-(RGB-J2-3)") (class "Default")
      (node (ref "Q11") (pin "2") (pinfunction "D_2") (pintype "passive"))
      (node (ref "RGB-J2") (pin "B") (pinfunction "3_B") (pintype "bidirectional"))
    )
    (net (code "69") (name "Net-(RGB-J2-4)") (class "Default")
      (node (ref "Q12") (pin "2") (pinfunction "D_2") (pintype "passive"))
      (node (ref "RGB-J2") (pin "G") (pinfunction "4_G") (pintype "bidirectional"))
    )
    (net (code "70") (name "Net-(U$1-DACL)") (class "Default")
      (node (ref "U$1") (pin "5") (pinfunction "DACL_5") (pintype "output"))
      (node (ref "X1") (pin "2") (pinfunction "2_2") (pintype "passive"))
    )
    (net (code "71") (name "Net-(U$1-DACR)") (class "Default")
      (node (ref "U$1") (pin "4") (pinfunction "DACR_4") (pintype "output"))
      (node (ref "X1") (pin "3") (pinfunction "3_3") (pintype "passive"))
    )
    (net (code "72") (name "Net-(U$1-RX)") (class "Default")
      (node (ref "R1") (pin "1") (pinfunction "1_1") (pintype "passive"))
      (node (ref "U$1") (pin "2") (pinfunction "RX_2") (pintype "input"))
    )
    (net (code "73") (name "Net-(U$1-TX)") (class "Default")
      (node (ref "R2") (pin "1") (pinfunction "1_1") (pintype "passive"))
      (node (ref "U$1") (pin "3") (pinfunction "TX_3") (pintype "output"))
    )
    (net (code "74") (name "Net-(U$3-RNU)") (class "Default")
      (node (ref "LED9") (pin "C") (pinfunction "C_C") (pintype "passive"))
      (node (ref "U$3") (pin "RUN") (pinfunction "RNU_RUN") (pintype "bidirectional"))
    )
    (net (code "75") (name "Net-(U$4-UCAP)") (class "Default")
      (node (ref "C3") (pin "2") (pinfunction "2_2") (pintype "passive"))
      (node (ref "U$4") (pin "6") (pinfunction "UCAP_6") (pintype "bidirectional"))
    )
    (net (code "76") (name "VUSB") (class "Default")
      (node (ref "C7") (pin "2") (pinfunction "2_2") (pintype "passive"))
      (node (ref "D4") (pin "A") (pinfunction "A_A") (pintype "passive"))
      (node (ref "U$4") (pin "7") (pinfunction "VBUS_7") (pintype "bidirectional"))
      (node (ref "X4") (pin "1") (pinfunction "1_1") (pintype "passive"))
    )
    (net (code "77") (name "unconnected-(CFG-Pad2)") (class "Default")
      (node (ref "CFG") (pin "2") (pinfunction "2_2") (pintype "passive"))
    )
    (net (code "78") (name "unconnected-(CFG-Pad3)") (class "Default")
      (node (ref "CFG") (pin "3") (pinfunction "3_3") (pintype "passive"))
    )
    (net (code "79") (name "unconnected-(Q1-D-Pad4)") (class "Default")
      (node (ref "Q1") (pin "4") (pinfunction "D_4") (pintype "passive"))
    )
    (net (code "80") (name "unconnected-(Q2-D-Pad4)") (class "Default")
      (node (ref "Q2") (pin "4") (pinfunction "D_4") (pintype "passive"))
    )
    (net (code "81") (name "unconnected-(Q4-D-Pad4)") (class "Default")
      (node (ref "Q4") (pin "4") (pinfunction "D_4") (pintype "passive"))
    )
    (net (code "82") (name "unconnected-(Q5-D-Pad4)") (class "Default")
      (node (ref "Q5") (pin "4") (pinfunction "D_4") (pintype "passive"))
    )
    (net (code "83") (name "unconnected-(Q6-D-Pad4)") (class "Default")
      (node (ref "Q6") (pin "4") (pinfunction "D_4") (pintype "passive"))
    )
    (net (code "84") (name "unconnected-(Q7-D-Pad4)") (class "Default")
      (node (ref "Q7") (pin "4") (pinfunction "D_4") (pintype "passive"))
    )
    (net (code "85") (name "unconnected-(Q8-D-Pad4)") (class "Default")
      (node (ref "Q8") (pin "4") (pinfunction "D_4") (pintype "passive"))
    )
    (net (code "86") (name "unconnected-(Q9-D-Pad4)") (class "Default")
      (node (ref "Q9") (pin "4") (pinfunction "D_4") (pintype "passive"))
    )
    (net (code "87") (name "unconnected-(Q10-D-Pad4)") (class "Default")
      (node (ref "Q10") (pin "4") (pinfunction "D_4") (pintype "passive"))
    )
    (net (code "88") (name "unconnected-(Q11-D-Pad4)") (class "Default")
      (node (ref "Q11") (pin "4") (pinfunction "D_4") (pintype "passive"))
    )
    (net (code "89") (name "unconnected-(Q12-D-Pad4)") (class "Default")
      (node (ref "Q12") (pin "4") (pinfunction "D_4") (pintype "passive"))
    )
    (net (code "90") (name "unconnected-(RESET1-Pad1)") (class "Default")
      (node (ref "RESET1") (pin "1") (pinfunction "1_1") (pintype "passive"))
    )
    (net (code "91") (name "unconnected-(RESET1-Pad3)") (class "Default")
      (node (ref "RESET1") (pin "3") (pinfunction "3_3") (pintype "passive"))
    )
    (net (code "92") (name "unconnected-(U$1-BUSY-Pad16)") (class "Default")
      (node (ref "U$1") (pin "16") (pinfunction "BUSY_16") (pintype "output"))
    )
    (net (code "93") (name "unconnected-(U$1-IO1-Pad9)") (class "Default")
      (node (ref "U$1") (pin "9") (pinfunction "IO1_9") (pintype "bidirectional"))
    )
    (net (code "94") (name "unconnected-(U$1-IO2-Pad11)") (class "Default")
      (node (ref "U$1") (pin "11") (pinfunction "IO2_11") (pintype "bidirectional"))
    )
    (net (code "95") (name "unconnected-(U$1-KEY1-Pad12)") (class "Default")
      (node (ref "U$1") (pin "12") (pinfunction "KEY1_12") (pintype "input"))
    )
    (net (code "96") (name "unconnected-(U$1-KEY2-Pad13)") (class "Default")
      (node (ref "U$1") (pin "13") (pinfunction "KEY2_13") (pintype "input"))
    )
    (net (code "97") (name "unconnected-(U$1-SPK1-Pad6)") (class "Default")
      (node (ref "U$1") (pin "6") (pinfunction "SPK1_6") (pintype "output"))
    )
    (net (code "98") (name "unconnected-(U$1-SPK2-Pad8)") (class "Default")
      (node (ref "U$1") (pin "8") (pinfunction "SPK2_8") (pintype "output"))
    )
    (net (code "99") (name "unconnected-(U$1-USB+-Pad14)") (class "Default")
      (node (ref "U$1") (pin "14") (pinfunction "USB+_14") (pintype "bidirectional"))
    )
    (net (code "100") (name "unconnected-(U$1-USB--Pad15)") (class "Default")
      (node (ref "U$1") (pin "15") (pinfunction "USB-_15") (pintype "bidirectional"))
    )
    (net (code "101") (name "unconnected-(U$3-PadRST)") (class "Default")
      (node (ref "U$3") (pin "RST") (pinfunction "RST_RST") (pintype "bidirectional"))
    )
    (net (code "102") (name "unconnected-(X1-Pad4)") (class "Default")
      (node (ref "X1") (pin "4") (pinfunction "4_4") (pintype "passive"))
    )
    (net (code "103") (name "unconnected-(X1-Pad5)") (class "Default")
      (node (ref "X1") (pin "5") (pinfunction "5_5") (pintype "passive"))
    )
    (net (code "104") (name "unconnected-(X4-Pad4)") (class "Default")
      (node (ref "X4") (pin "4") (pinfunction "4_4") (pintype "passive"))
    )
  )
)
